# RFID_v0_3.net
KiCad netlist of a schematic drawn in EAGLE
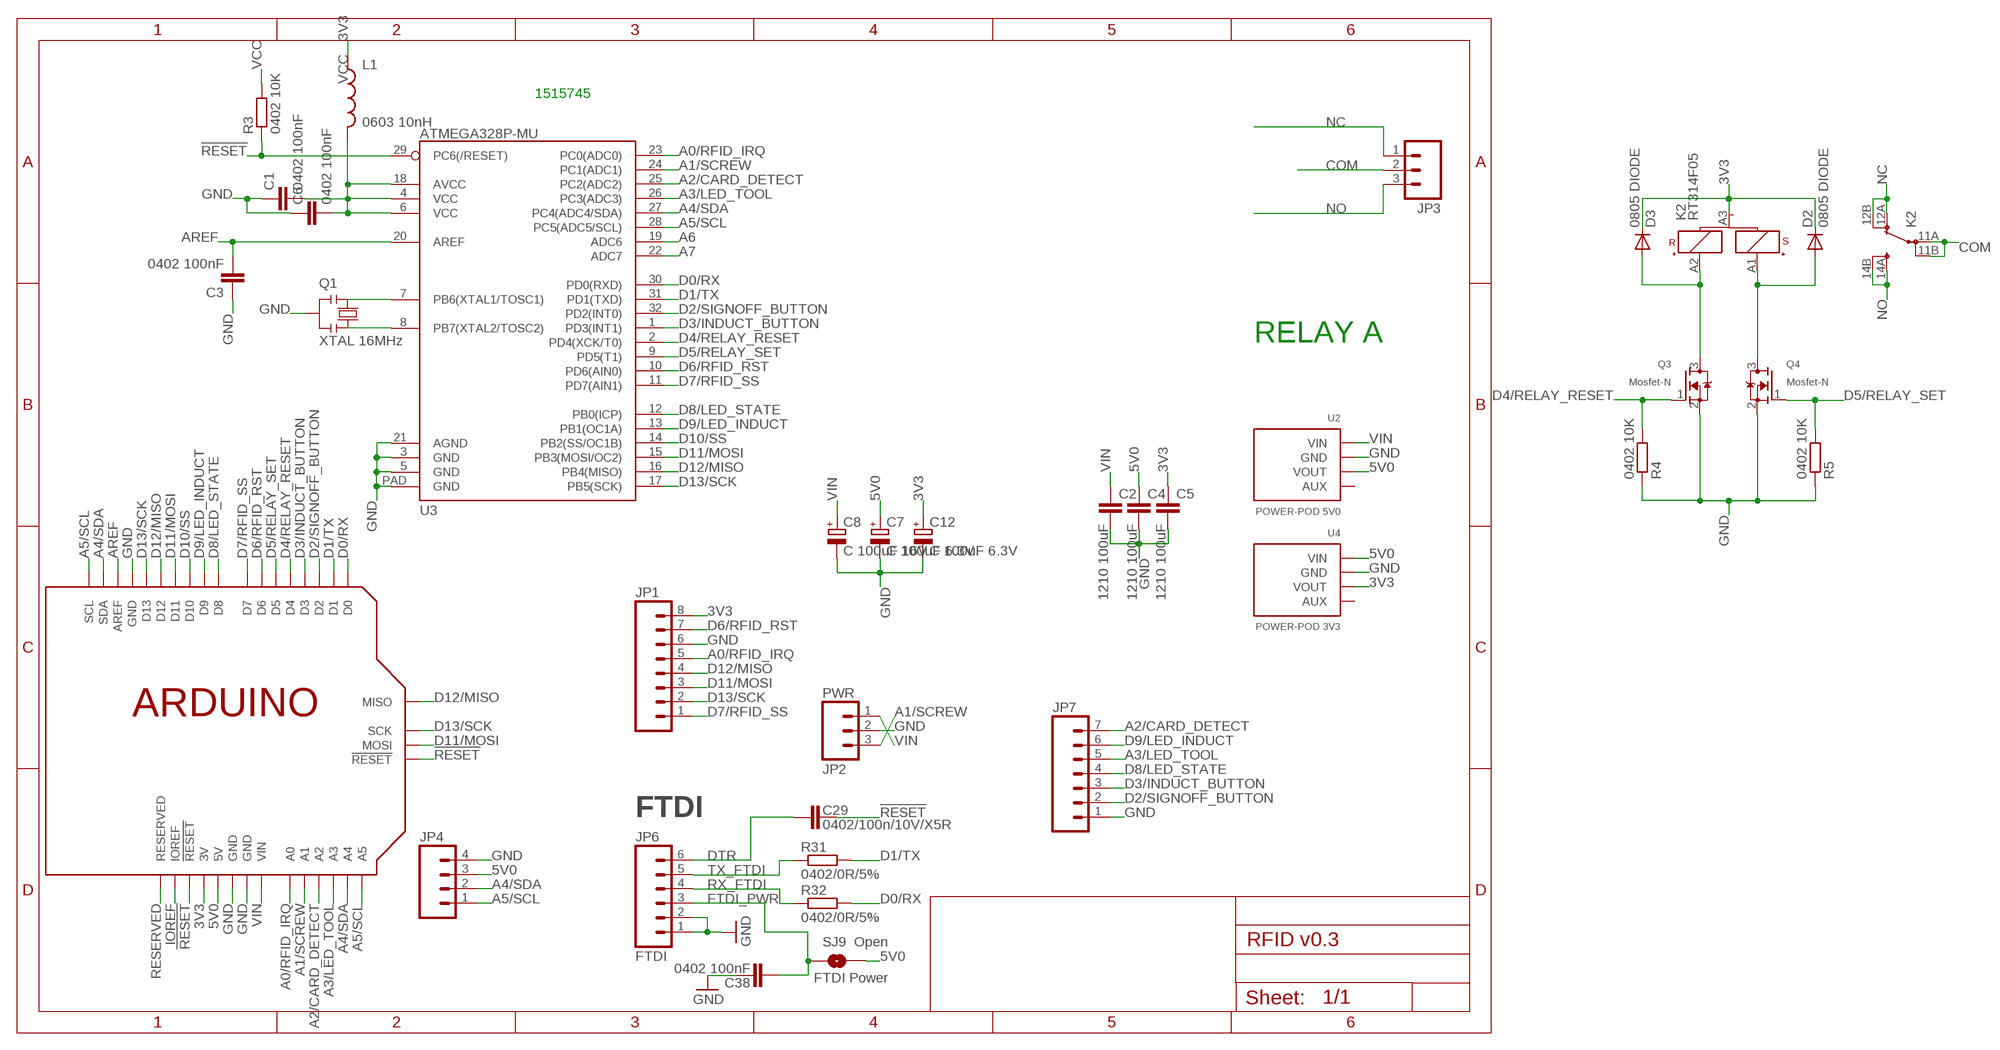
[diagram p0: schematic, sheet 1]

(export (version "E")
  (design (tool "Eeschema 10.0.6"))
  (components
    (comp (ref "C1")
      (value "0402 100nF")
      (footprint "eagle-import:C0402-SMALLER")
      (libsource (lib "eagle-import") (part "C-EUC0402-SMALLER"))
    )
    (comp (ref "C2")
      (value "1210 100uF")
      (footprint "eagle-import:C1210")
      (libsource (lib "eagle-import") (part "C-EUC1210"))
    )
    (comp (ref "C3")
      (value "0402 100nF")
      (footprint "eagle-import:C0402-SMALLER")
      (libsource (lib "eagle-import") (part "C-EUC0402-SMALLER"))
    )
    (comp (ref "C4")
      (value "1210 100uF")
      (footprint "eagle-import:C1210")
      (libsource (lib "eagle-import") (part "C-EUC1210"))
    )
    (comp (ref "C5")
      (value "1210 100uF")
      (footprint "eagle-import:C1210")
      (libsource (lib "eagle-import") (part "C-EUC1210"))
    )
    (comp (ref "C6")
      (value "0402 100nF")
      (footprint "eagle-import:C0402-SMALLER")
      (libsource (lib "eagle-import") (part "C-EUC0402-SMALLER"))
    )
    (comp (ref "C7")
      (value "C 100uF 6.3V")
      (footprint "eagle-import:PANASONIC_C")
      (libsource (lib "eagle-import") (part "CPOL-EUC"))
    )
    (comp (ref "C8")
      (value "C 100uF 16V")
      (footprint "eagle-import:PANASONIC_C")
      (libsource (lib "eagle-import") (part "CPOL-EUC"))
    )
    (comp (ref "C12")
      (value "C 100uF 6.3V")
      (footprint "eagle-import:PANASONIC_C")
      (libsource (lib "eagle-import") (part "CPOL-EUC"))
    )
    (comp (ref "C29")
      (value "0402/100n/10V/X5R")
      (footprint "eagle-import:C0402-ARDUINO-ROUND")
      (libsource (lib "eagle-import") (part "TiLDA Mk2 Parts_C-EUC0402-ARDUINO-ROUND"))
    )
    (comp (ref "C38")
      (value "0402 100nF")
      (footprint "eagle-import:C0402-SMALLER")
      (libsource (lib "eagle-import") (part "TiLDA Mk2 Parts_C-EUC0402-SMALLER"))
    )
    (comp (ref "D2")
      (value "0805 DIODE")
      (footprint "eagle-import:0805-DIODE")
      (libsource (lib "eagle-import") (part "DIODE-0805"))
    )
    (comp (ref "D3")
      (value "0805 DIODE")
      (footprint "eagle-import:0805-DIODE")
      (libsource (lib "eagle-import") (part "DIODE-0805"))
    )
    (comp (ref "JP1")
      (value "M081X08")
      (footprint "eagle-import:1X08")
      (libsource (lib "eagle-import") (part "M081X08"))
    )
    (comp (ref "JP2")
      (value "PWR")
      (footprint "eagle-import:SCREWTERMINAL-5MM-3")
      (libsource (lib "eagle-import") (part "M03-SCREW-5MM"))
    )
    (comp (ref "JP3")
      (value "M03-SCREW-5MM")
      (footprint "eagle-import:SCREWTERMINAL-5MM-3")
      (libsource (lib "eagle-import") (part "M03-SCREW-5MM"))
    )
    (comp (ref "JP4")
      (value "M04PTH")
      (footprint "eagle-import:1X04")
      (libsource (lib "eagle-import") (part "M04PTH"))
    )
    (comp (ref "JP6")
      (value "FTDI")
      (footprint "eagle-import:1X06")
      (libsource (lib "eagle-import") (part "M06SIP"))
    )
    (comp (ref "JP7")
      (value "M07")
      (footprint "eagle-import:1X07")
      (libsource (lib "eagle-import") (part "M07"))
    )
    (comp (ref "K2")
      (value "RT314F05")
      (footprint "eagle-import:RT1-BI")
      (libsource (lib "eagle-import") (part "RT?F31405"))
    )
    (comp (ref "L1")
      (value "0603 10nH")
      (footprint "eagle-import:C0603K-SMALL")
      (libsource (lib "eagle-import") (part "INDUCTOR0603K-SMALL"))
    )
    (comp (ref "Q1")
      (value "XTAL 16MHz")
      (footprint "eagle-import:RESONATOR")
      (libsource (lib "eagle-import") (part "RESONATORMU"))
    )
    (comp (ref "Q3")
      (value "Mosfet-N")
      (footprint "eagle-import:SOT23-3")
      (libsource (lib "eagle-import") (part "MOSFET-N-SOT23-SPARK"))
    )
    (comp (ref "Q4")
      (value "Mosfet-N")
      (footprint "eagle-import:SOT23-3")
      (libsource (lib "eagle-import") (part "MOSFET-N-SOT23-SPARK"))
    )
    (comp (ref "R3")
      (value "0402 10K")
      (footprint "eagle-import:R0402-SMALLER")
      (libsource (lib "eagle-import") (part "R-EU_R0402-SMALLER"))
    )
    (comp (ref "R4")
      (value "0402 10K")
      (footprint "eagle-import:R0402-SMALLER")
      (libsource (lib "eagle-import") (part "R-EU_R0402-SMALLER"))
    )
    (comp (ref "R5")
      (value "0402 10K")
      (footprint "eagle-import:R0402-SMALLER")
      (libsource (lib "eagle-import") (part "R-EU_R0402-SMALLER"))
    )
    (comp (ref "R31")
      (value "0402/0R/5%")
      (footprint "eagle-import:R0402-ARDUINO-ROUND")
      (libsource (lib "eagle-import") (part "R-EU_R0402-ARDUINO-ROUND"))
    )
    (comp (ref "R32")
      (value "0402/0R/5%")
      (footprint "eagle-import:R0402-ARDUINO-ROUND")
      (libsource (lib "eagle-import") (part "R-EU_R0402-ARDUINO-ROUND"))
    )
    (comp (ref "SJ9")
      (value "FTDI Power")
      (footprint "eagle-import:SJ_2S-NO")
      (libsource (lib "eagle-import") (part "SOLDERJUMPERNO"))
    )
    (comp (ref "U1")
      (value "ARDUINOSPI-REFRENCE")
      (footprint "eagle-import:ARDUINOR3-LWKTXT-REF-SPI")
      (libsource (lib "eagle-import") (part "ARDUINOSPI-REFRENCE"))
    )
    (comp (ref "U2")
      (value "POWER-POD 5V0")
      (footprint "eagle-import:POWER-POD-LANDING")
      (libsource (lib "eagle-import") (part "POWER-POD"))
    )
    (comp (ref "U3")
      (value "ATMEGA328P-MU")
      (footprint "eagle-import:MLF32-SHORT-CREAM")
      (libsource (lib "eagle-import") (part "ATMEGA328-MLF-SHORT"))
    )
    (comp (ref "U4")
      (value "POWER-POD 3V3")
      (footprint "eagle-import:POWER-POD-LANDING")
      (libsource (lib "eagle-import") (part "POWER-POD"))
    )
  )
  (nets
    (net (code "1") (name "/3V3") (class "Default")
      (node (ref "C12") (pin "+") (pinfunction "+_+") (pintype "passive"))
      (node (ref "C5") (pin "1") (pinfunction "1_1") (pintype "passive"))
      (node (ref "D2") (pin "C") (pinfunction "C_C") (pintype "passive"))
      (node (ref "D3") (pin "C") (pinfunction "C_C") (pintype "passive"))
      (node (ref "JP1") (pin "8") (pinfunction "8_8") (pintype "passive"))
      (node (ref "K2") (pin "A3") (pinfunction "-_A3") (pintype "passive"))
      (node (ref "L1") (pin "1") (pinfunction "1_1") (pintype "passive"))
      (node (ref "U1") (pin "3V") (pinfunction "3V_3V") (pintype "power_in"))
      (node (ref "U4") (pin "3") (pinfunction "VOUT_3") (pintype "bidirectional"))
    )
    (net (code "2") (name "/5V0") (class "Default")
      (node (ref "C4") (pin "1") (pinfunction "1_1") (pintype "passive"))
      (node (ref "C7") (pin "+") (pinfunction "+_+") (pintype "passive"))
      (node (ref "JP4") (pin "3") (pinfunction "3_3") (pintype "passive"))
      (node (ref "SJ9") (pin "2") (pinfunction "2_2") (pintype "passive"))
      (node (ref "U1") (pin "5V") (pinfunction "5V_5V") (pintype "power_in"))
      (node (ref "U1") (pin "5V@ISP") (pinfunction "5V_5V@ISP") (pintype "power_in"))
      (node (ref "U2") (pin "3") (pinfunction "VOUT_3") (pintype "bidirectional"))
      (node (ref "U4") (pin "1") (pinfunction "VIN_1") (pintype "bidirectional"))
    )
    (net (code "3") (name "/A0{slash}RFID_IRQ") (class "Default")
      (node (ref "JP1") (pin "5") (pinfunction "5_5") (pintype "passive"))
      (node (ref "U1") (pin "A0") (pinfunction "A0_A0") (pintype "bidirectional"))
      (node (ref "U3") (pin "23") (pinfunction "PC0(ADC0)_23") (pintype "bidirectional"))
    )
    (net (code "4") (name "/A1{slash}SCREW") (class "Default")
      (node (ref "JP2") (pin "3") (pinfunction "3_3") (pintype "passive"))
      (node (ref "U1") (pin "A1") (pinfunction "A1_A1") (pintype "bidirectional"))
      (node (ref "U3") (pin "24") (pinfunction "PC1(ADC1)_24") (pintype "bidirectional"))
    )
    (net (code "5") (name "/A2{slash}CARD_DETECT") (class "Default")
      (node (ref "JP7") (pin "7") (pinfunction "7_7") (pintype "passive"))
      (node (ref "U1") (pin "A2") (pinfunction "A2_A2") (pintype "bidirectional"))
      (node (ref "U3") (pin "25") (pinfunction "PC2(ADC2)_25") (pintype "bidirectional"))
    )
    (net (code "6") (name "/A3{slash}LED_TOOL") (class "Default")
      (node (ref "JP7") (pin "5") (pinfunction "5_5") (pintype "passive"))
      (node (ref "U1") (pin "A3") (pinfunction "A3_A3") (pintype "bidirectional"))
      (node (ref "U3") (pin "26") (pinfunction "PC3(ADC3)_26") (pintype "bidirectional"))
    )
    (net (code "7") (name "/A4{slash}SDA") (class "Default")
      (node (ref "JP4") (pin "2") (pinfunction "2_2") (pintype "passive"))
      (node (ref "U1") (pin "A4") (pinfunction "A4_A4") (pintype "bidirectional"))
      (node (ref "U1") (pin "SDA") (pinfunction "SDA_SDA") (pintype "bidirectional"))
      (node (ref "U3") (pin "27") (pinfunction "PC4(ADC4/SDA)_27") (pintype "bidirectional"))
    )
    (net (code "8") (name "/A5{slash}SCL") (class "Default")
      (node (ref "JP4") (pin "1") (pinfunction "1_1") (pintype "passive"))
      (node (ref "U1") (pin "A5") (pinfunction "A5_A5") (pintype "bidirectional"))
      (node (ref "U1") (pin "SCL") (pinfunction "SCL_SCL") (pintype "bidirectional"))
      (node (ref "U3") (pin "28") (pinfunction "PC5(ADC5/SCL)_28") (pintype "bidirectional"))
    )
    (net (code "9") (name "/A6") (class "Default")
      (node (ref "U3") (pin "19") (pinfunction "ADC6_19") (pintype "bidirectional"))
    )
    (net (code "10") (name "/A7") (class "Default")
      (node (ref "U3") (pin "22") (pinfunction "ADC7_22") (pintype "bidirectional"))
    )
    (net (code "11") (name "/AREF") (class "Default")
      (node (ref "C3") (pin "2") (pinfunction "2_2") (pintype "passive"))
      (node (ref "U1") (pin "AREF") (pinfunction "AREF_AREF") (pintype "bidirectional"))
      (node (ref "U3") (pin "20") (pinfunction "AREF_20") (pintype "bidirectional"))
    )
    (net (code "12") (name "/COM") (class "Default")
      (node (ref "JP3") (pin "2") (pinfunction "2_2") (pintype "passive"))
      (node (ref "K2") (pin "11A") (pinfunction "PA_11A") (pintype "passive"))
      (node (ref "K2") (pin "11B") (pinfunction "PB_11B") (pintype "passive"))
    )
    (net (code "13") (name "/D0{slash}RX") (class "Default")
      (node (ref "R32") (pin "2") (pinfunction "2_2") (pintype "passive"))
      (node (ref "U1") (pin "D0") (pinfunction "D0_D0") (pintype "bidirectional"))
      (node (ref "U3") (pin "30") (pinfunction "PD0(RXD)_30") (pintype "bidirectional"))
    )
    (net (code "14") (name "/D1{slash}TX") (class "Default")
      (node (ref "R31") (pin "2") (pinfunction "2_2") (pintype "passive"))
      (node (ref "U1") (pin "D1") (pinfunction "D1_D1") (pintype "bidirectional"))
      (node (ref "U3") (pin "31") (pinfunction "PD1(TXD)_31") (pintype "bidirectional"))
    )
    (net (code "15") (name "/D2{slash}SIGNOFF_BUTTON") (class "Default")
      (node (ref "JP7") (pin "2") (pinfunction "2_2") (pintype "passive"))
      (node (ref "U1") (pin "D2") (pinfunction "D2_D2") (pintype "bidirectional"))
      (node (ref "U3") (pin "32") (pinfunction "PD2(INT0)_32") (pintype "bidirectional"))
    )
    (net (code "16") (name "/D3{slash}INDUCT_BUTTON") (class "Default")
      (node (ref "JP7") (pin "3") (pinfunction "3_3") (pintype "passive"))
      (node (ref "U1") (pin "D3") (pinfunction "D3_D3") (pintype "bidirectional"))
      (node (ref "U3") (pin "1") (pinfunction "PD3(INT1)_1") (pintype "bidirectional"))
    )
    (net (code "17") (name "/D4{slash}RELAY_RESET") (class "Default")
      (node (ref "Q3") (pin "1") (pinfunction "G_1") (pintype "bidirectional"))
      (node (ref "R4") (pin "2") (pinfunction "2_2") (pintype "passive"))
      (node (ref "U1") (pin "D4") (pinfunction "D4_D4") (pintype "bidirectional"))
      (node (ref "U3") (pin "2") (pinfunction "PD4(XCK/T0)_2") (pintype "bidirectional"))
    )
    (net (code "18") (name "/D5{slash}RELAY_SET") (class "Default")
      (node (ref "Q4") (pin "1") (pinfunction "G_1") (pintype "bidirectional"))
      (node (ref "R5") (pin "2") (pinfunction "2_2") (pintype "passive"))
      (node (ref "U1") (pin "D5") (pinfunction "D5_D5") (pintype "bidirectional"))
      (node (ref "U3") (pin "9") (pinfunction "PD5(T1)_9") (pintype "bidirectional"))
    )
    (net (code "19") (name "/D6{slash}RFID_RST") (class "Default")
      (node (ref "JP1") (pin "7") (pinfunction "7_7") (pintype "passive"))
      (node (ref "U1") (pin "D6") (pinfunction "D6_D6") (pintype "bidirectional"))
      (node (ref "U3") (pin "10") (pinfunction "PD6(AIN0)_10") (pintype "bidirectional"))
    )
    (net (code "20") (name "/D7{slash}RFID_SS") (class "Default")
      (node (ref "JP1") (pin "1") (pinfunction "1_1") (pintype "passive"))
      (node (ref "U1") (pin "D7") (pinfunction "D7_D7") (pintype "bidirectional"))
      (node (ref "U3") (pin "11") (pinfunction "PD7(AIN1)_11") (pintype "bidirectional"))
    )
    (net (code "21") (name "/D8{slash}LED_STATE") (class "Default")
      (node (ref "JP7") (pin "4") (pinfunction "4_4") (pintype "passive"))
      (node (ref "U1") (pin "D8") (pinfunction "D8_D8") (pintype "bidirectional"))
      (node (ref "U3") (pin "12") (pinfunction "PB0(ICP)_12") (pintype "bidirectional"))
    )
    (net (code "22") (name "/D9{slash}LED_INDUCT") (class "Default")
      (node (ref "JP7") (pin "6") (pinfunction "6_6") (pintype "passive"))
      (node (ref "U1") (pin "D9") (pinfunction "D9_D9") (pintype "bidirectional"))
      (node (ref "U3") (pin "13") (pinfunction "PB1(OC1A)_13") (pintype "bidirectional"))
    )
    (net (code "23") (name "/D10{slash}SS") (class "Default")
      (node (ref "U1") (pin "D10") (pinfunction "D10_D10") (pintype "bidirectional"))
      (node (ref "U3") (pin "14") (pinfunction "PB2(SS/OC1B)_14") (pintype "bidirectional"))
    )
    (net (code "24") (name "/D11{slash}MOSI") (class "Default")
      (node (ref "JP1") (pin "3") (pinfunction "3_3") (pintype "passive"))
      (node (ref "U1") (pin "D11") (pinfunction "D11_D11") (pintype "bidirectional"))
      (node (ref "U1") (pin "MOSI") (pinfunction "MOSI_MOSI") (pintype "bidirectional"))
      (node (ref "U3") (pin "15") (pinfunction "PB3(MOSI/OC2)_15") (pintype "bidirectional"))
    )
    (net (code "25") (name "/D12{slash}MISO") (class "Default")
      (node (ref "JP1") (pin "4") (pinfunction "4_4") (pintype "passive"))
      (node (ref "U1") (pin "D12") (pinfunction "D12_D12") (pintype "bidirectional"))
      (node (ref "U1") (pin "MISO") (pinfunction "MISO_MISO") (pintype "bidirectional"))
      (node (ref "U3") (pin "16") (pinfunction "PB4(MISO)_16") (pintype "bidirectional"))
    )
    (net (code "26") (name "/D13{slash}SCK") (class "Default")
      (node (ref "JP1") (pin "2") (pinfunction "2_2") (pintype "passive"))
      (node (ref "U1") (pin "D13") (pinfunction "D13_D13") (pintype "bidirectional"))
      (node (ref "U1") (pin "SCK") (pinfunction "SCK_SCK") (pintype "bidirectional"))
      (node (ref "U3") (pin "17") (pinfunction "PB5(SCK)_17") (pintype "bidirectional"))
    )
    (net (code "27") (name "/DTR") (class "Default")
      (node (ref "C29") (pin "2") (pinfunction "2_2") (pintype "passive"))
      (node (ref "JP6") (pin "6") (pinfunction "6_6") (pintype "passive"))
    )
    (net (code "28") (name "/FTDI_PWR") (class "Default")
      (node (ref "C38") (pin "2") (pinfunction "2_2") (pintype "passive"))
      (node (ref "JP6") (pin "3") (pinfunction "3_3") (pintype "passive"))
      (node (ref "SJ9") (pin "1") (pinfunction "1_1") (pintype "passive"))
    )
    (net (code "29") (name "/IOREF") (class "Default")
      (node (ref "U1") (pin "IOREF") (pinfunction "IOREF_IOREF") (pintype "output"))
    )
    (net (code "30") (name "/NC") (class "Default")
      (node (ref "JP3") (pin "1") (pinfunction "1_1") (pintype "passive"))
      (node (ref "K2") (pin "12A") (pinfunction "OA_12A") (pintype "passive"))
      (node (ref "K2") (pin "12B") (pinfunction "OB_12B") (pintype "passive"))
    )
    (net (code "31") (name "/NO") (class "Default")
      (node (ref "JP3") (pin "3") (pinfunction "3_3") (pintype "passive"))
      (node (ref "K2") (pin "14A") (pinfunction "SA_14A") (pintype "passive"))
      (node (ref "K2") (pin "14B") (pinfunction "SB_14B") (pintype "passive"))
    )
    (net (code "33") (name "/RX_FTDI") (class "Default")
      (node (ref "JP6") (pin "4") (pinfunction "4_4") (pintype "passive"))
      (node (ref "R32") (pin "1") (pinfunction "1_1") (pintype "passive"))
    )
    (net (code "34") (name "/TX_FTDI") (class "Default")
      (node (ref "JP6") (pin "5") (pinfunction "5_5") (pintype "passive"))
      (node (ref "R31") (pin "1") (pinfunction "1_1") (pintype "passive"))
    )
    (net (code "35") (name "/VCC") (class "Default")
      (node (ref "C1") (pin "2") (pinfunction "2_2") (pintype "passive"))
      (node (ref "C6") (pin "2") (pinfunction "2_2") (pintype "passive"))
      (node (ref "L1") (pin "2") (pinfunction "2_2") (pintype "passive"))
      (node (ref "R3") (pin "2") (pinfunction "2_2") (pintype "passive"))
      (node (ref "U3") (pin "18") (pinfunction "AVCC_18") (pintype "bidirectional"))
      (node (ref "U3") (pin "4") (pinfunction "VCC_4") (pintype "bidirectional"))
      (node (ref "U3") (pin "6") (pinfunction "VCC_6") (pintype "bidirectional"))
    )
    (net (code "36") (name "/VIN") (class "Default")
      (node (ref "C2") (pin "1") (pinfunction "1_1") (pintype "passive"))
      (node (ref "C8") (pin "+") (pinfunction "+_+") (pintype "passive"))
      (node (ref "JP2") (pin "1") (pinfunction "1_1") (pintype "passive"))
      (node (ref "U1") (pin "VIN") (pinfunction "VIN_VIN") (pintype "power_in"))
      (node (ref "U2") (pin "1") (pinfunction "VIN_1") (pintype "bidirectional"))
    )
    (net (code "37") (name "/~{RESET}") (class "Default")
      (node (ref "C29") (pin "1") (pinfunction "1_1") (pintype "passive"))
      (node (ref "R3") (pin "1") (pinfunction "1_1") (pintype "passive"))
      (node (ref "U1") (pin "!RESET") (pinfunction "~{RESET}_!RESET") (pintype "bidirectional"))
      (node (ref "U1") (pin "!RESET@ISP") (pinfunction "~{RESET}_!RESET@ISP") (pintype "bidirectional"))
      (node (ref "U3") (pin "29") (pinfunction "PC6(/RESET)_29") (pintype "bidirectional"))
    )
    (net (code "38") (name "GND") (class "Default")
      (node (ref "C1") (pin "1") (pinfunction "1_1") (pintype "passive"))
      (node (ref "C12") (pin "-") (pinfunction "-_-") (pintype "passive"))
      (node (ref "C2") (pin "2") (pinfunction "2_2") (pintype "passive"))
      (node (ref "C3") (pin "1") (pinfunction "1_1") (pintype "passive"))
      (node (ref "C38") (pin "1") (pinfunction "1_1") (pintype "passive"))
      (node (ref "C4") (pin "2") (pinfunction "2_2") (pintype "passive"))
      (node (ref "C5") (pin "2") (pinfunction "2_2") (pintype "passive"))
      (node (ref "C6") (pin "1") (pinfunction "1_1") (pintype "passive"))
      (node (ref "C7") (pin "-") (pinfunction "-_-") (pintype "passive"))
      (node (ref "C8") (pin "-") (pinfunction "-_-") (pintype "passive"))
      (node (ref "JP1") (pin "6") (pinfunction "6_6") (pintype "passive"))
      (node (ref "JP2") (pin "2") (pinfunction "2_2") (pintype "passive"))
      (node (ref "JP4") (pin "4") (pinfunction "4_4") (pintype "passive"))
      (node (ref "JP6") (pin "1") (pinfunction "1_1") (pintype "passive"))
      (node (ref "JP6") (pin "2") (pinfunction "2_2") (pintype "passive"))
      (node (ref "JP7") (pin "1") (pinfunction "1_1") (pintype "passive"))
      (node (ref "Q1") (pin "2") (pinfunction "2_2") (pintype "passive"))
      (node (ref "Q3") (pin "2") (pinfunction "S_2") (pintype "bidirectional"))
      (node (ref "Q4") (pin "2") (pinfunction "S_2") (pintype "bidirectional"))
      (node (ref "R4") (pin "1") (pinfunction "1_1") (pintype "passive"))
      (node (ref "R5") (pin "1") (pinfunction "1_1") (pintype "passive"))
      (node (ref "U1") (pin "GND@1") (pinfunction "GND_GND@1") (pintype "power_in"))
      (node (ref "U1") (pin "GND@2") (pinfunction "GND_GND@2") (pintype "power_in"))
      (node (ref "U1") (pin "GND@3") (pinfunction "GND_GND@3") (pintype "power_in"))
      (node (ref "U1") (pin "GND@ISP") (pinfunction "GND_GND@ISP") (pintype "power_in"))
      (node (ref "U2") (pin "2") (pinfunction "GND_2") (pintype "bidirectional"))
      (node (ref "U3") (pin "21") (pinfunction "AGND_21") (pintype "bidirectional"))
      (node (ref "U3") (pin "3") (pinfunction "GND_3") (pintype "bidirectional"))
      (node (ref "U3") (pin "5") (pinfunction "GND_5") (pintype "bidirectional"))
      (node (ref "U3") (pin "PAD") (pinfunction "GND_PAD") (pintype "bidirectional"))
      (node (ref "U4") (pin "2") (pinfunction "GND_2") (pintype "bidirectional"))
    )
    (net (code "39") (name "Net-(K2A-R+)") (class "Default")
      (node (ref "D3") (pin "A") (pinfunction "A_A") (pintype "passive"))
      (node (ref "K2") (pin "A2") (pinfunction "R+_A2") (pintype "passive"))
      (node (ref "Q3") (pin "3") (pinfunction "D_3") (pintype "bidirectional"))
    )
    (net (code "40") (name "Net-(K2A-S+)") (class "Default")
      (node (ref "D2") (pin "A") (pinfunction "A_A") (pintype "passive"))
      (node (ref "K2") (pin "A1") (pinfunction "S+_A1") (pintype "passive"))
      (node (ref "Q4") (pin "3") (pinfunction "D_3") (pintype "bidirectional"))
    )
    (net (code "41") (name "Net-(U3-PB6(XTAL1{slash}TOSC1))") (class "Default")
      (node (ref "Q1") (pin "1") (pinfunction "1_1") (pintype "passive"))
      (node (ref "U3") (pin "7") (pinfunction "PB6(XTAL1/TOSC1)_7") (pintype "bidirectional"))
    )
    (net (code "42") (name "Net-(U3-PB7(XTAL2{slash}TOSC2))") (class "Default")
      (node (ref "Q1") (pin "3") (pinfunction "3_3") (pintype "passive"))
      (node (ref "U3") (pin "8") (pinfunction "PB7(XTAL2/TOSC2)_8") (pintype "bidirectional"))
    )
    (net (code "43") (name "unconnected-(U1-PadRESERVED)") (class "Default")
      (node (ref "U1") (pin "RESERVED") (pinfunction "RESERVED_RESERVED") (pintype "no_connect"))
    )
    (net (code "44") (name "unconnected-(U2-AUX-Pad4)") (class "Default")
      (node (ref "U2") (pin "4") (pinfunction "AUX_4") (pintype "bidirectional"))
    )
    (net (code "45") (name "unconnected-(U4-AUX-Pad4)") (class "Default")
      (node (ref "U4") (pin "4") (pinfunction "AUX_4") (pintype "bidirectional"))
    )
  )
)
